# LTC2949_Connectors.net
KiCad netlist of a schematic drawn in Altium Designer
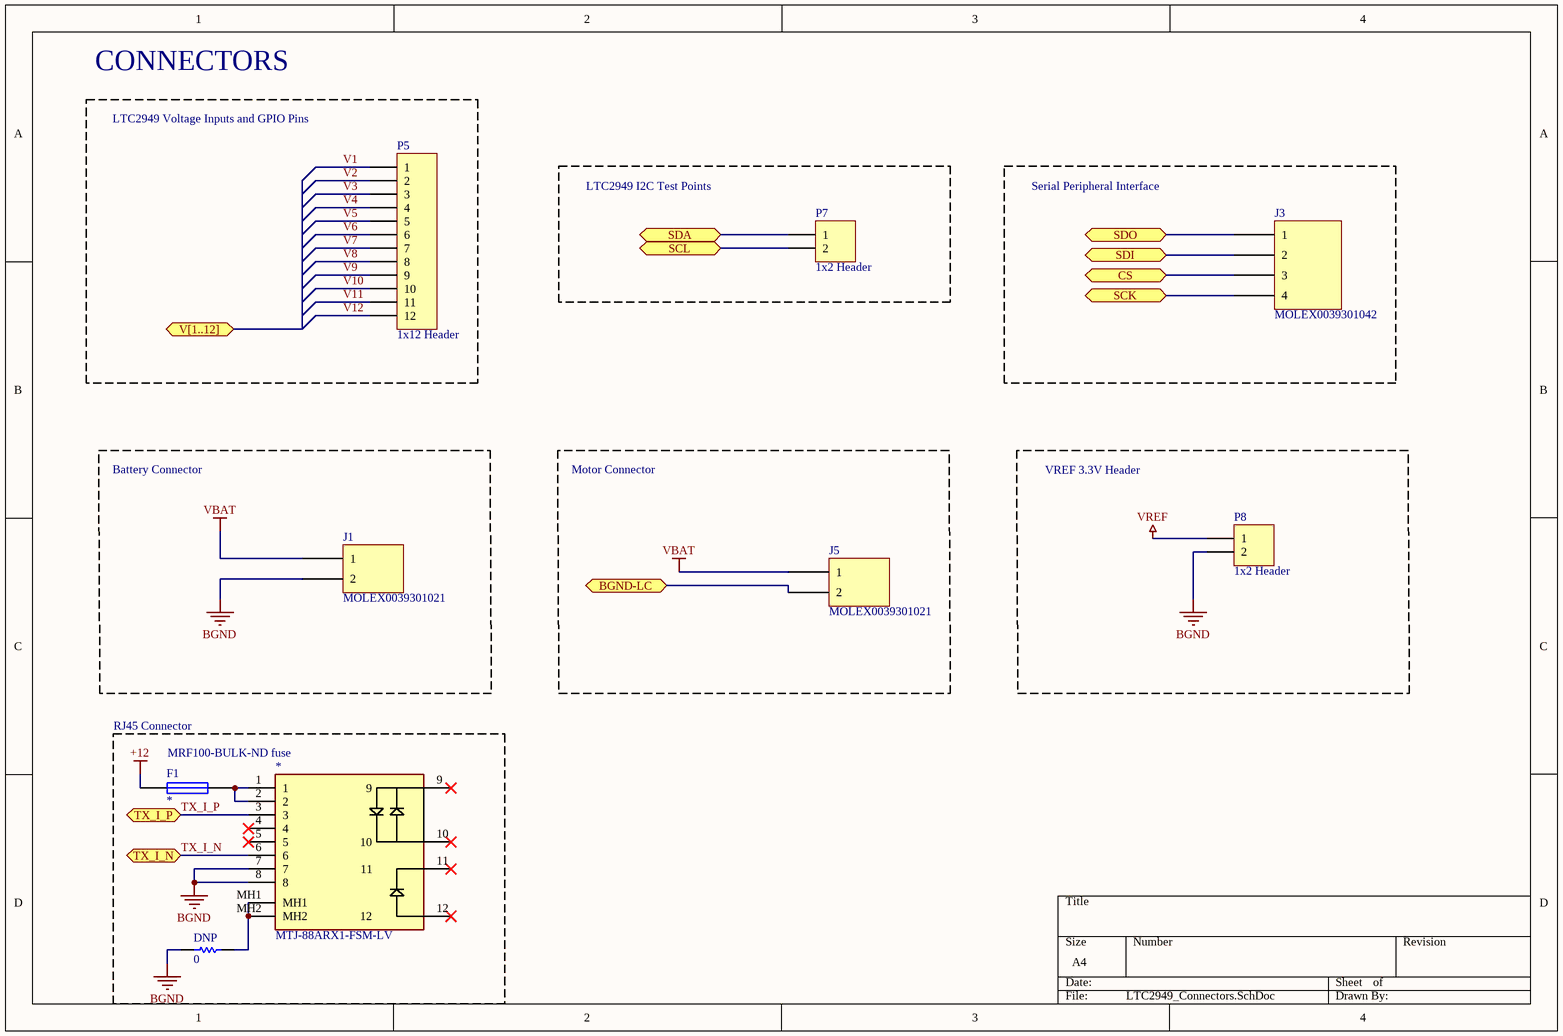
[diagram p0: LTC2949_Connectors.SchDoc]

(export (version "E")
  (design (tool "Eeschema 10.0.6"))
  (components
    (comp (ref "*")
      (value "MTJ-88ARX1-FSM-LV")
      (footprint "MTJ-88ARX1-FSM-LV")
      (description "RJ45 Connector")
      (libsource (lib "GeneralConnectors") (part "MTJ-88ARX1-FSM-LV"))
    )
    (comp (ref "DNP")
      (value "0")
      (footprint "0603 - Resistor")
      (description "Resistor")
      (libsource (lib "General") (part "Resistor"))
    )
    (comp (ref "F1")
      (value "Fuse")
      (footprint "3557-2")
      (fields (field (name "ALTIUM_VALUE") "*"))
      (libsource (lib "General") (part "Fuse"))
    )
    (comp (ref "J1")
      (value "MOLEX0039301021")
      (footprint "MOLEX0039301021")
      (description "Connector Header Through Hole, Right Angle 2 pin 0.165\" (4.20mm)")
      (libsource (lib "GeneralConnectors") (part "MOLEX0039301021"))
    )
    (comp (ref "J3")
      (value "MOLEX0039301042")
      (footprint "MOLEX0039301042")
      (description "Connector Header Through Hole, Right Angle 4 position 0.165\" (4.20mm)")
      (fields (field (name "MANUFACTURER") "Molex") (field (name "MANUFACTURER PART NUMBER") "0039301042"))
      (libsource (lib "GeneralConnectors") (part "MOLEX0039301042"))
    )
    (comp (ref "J5")
      (value "MOLEX0039301021")
      (footprint "MOLEX0039301021")
      (description "Connector Header Through Hole, Right Angle 2 pin 0.165\" (4.20mm)")
      (libsource (lib "GeneralConnectors") (part "MOLEX0039301021"))
    )
    (comp (ref "P5")
      (value "1x12 Header")
      (footprint "HDR1X12")
      (description "1x12 Pin Header")
      (libsource (lib "GeneralConnectors") (part "1x12 Header"))
    )
    (comp (ref "P7")
      (value "1x2 Header")
      (footprint "HDR1X2")
      (description "1x2 Pin Header")
      (libsource (lib "GeneralConnectors") (part "1x2 Header"))
    )
    (comp (ref "P8")
      (value "1x2 Header")
      (footprint "HDR1X2")
      (description "1x2 Pin Header")
      (libsource (lib "GeneralConnectors") (part "1x2 Header"))
    )
  )
  (nets
    (net (code "1") (name "+12") (class "Default")
      (node (ref "F1") (pin "1") (pinfunction "1_1") (pintype "passive"))
    )
    (net (code "2") (name "/BGND-LC") (class "Default")
      (node (ref "J5") (pin "2") (pinfunction "2_2") (pintype "passive"))
    )
    (net (code "3") (name "/CS") (class "Default")
      (node (ref "J3") (pin "3") (pinfunction "3_3") (pintype "passive"))
    )
    (net (code "4") (name "/SCK") (class "Default")
      (node (ref "J3") (pin "4") (pinfunction "4_4") (pintype "passive"))
    )
    (net (code "5") (name "/SCL") (class "Default")
      (node (ref "P7") (pin "2") (pinfunction "2_2") (pintype "passive"))
    )
    (net (code "6") (name "/SDA") (class "Default")
      (node (ref "P7") (pin "1") (pinfunction "1_1") (pintype "passive"))
    )
    (net (code "7") (name "/SDI") (class "Default")
      (node (ref "J3") (pin "2") (pinfunction "2_2") (pintype "passive"))
    )
    (net (code "8") (name "/SDO") (class "Default")
      (node (ref "J3") (pin "1") (pinfunction "1_1") (pintype "passive"))
    )
    (net (code "9") (name "/TX_I_N") (class "Default")
      (node (ref "*") (pin "6") (pinfunction "6_6") (pintype "passive"))
    )
    (net (code "10") (name "/TX_I_P") (class "Default")
      (node (ref "*") (pin "3") (pinfunction "3_3") (pintype "passive"))
    )
    (net (code "11") (name "/V1") (class "Default")
      (node (ref "P5") (pin "1") (pinfunction "1_1") (pintype "passive"))
    )
    (net (code "12") (name "/V2") (class "Default")
      (node (ref "P5") (pin "2") (pinfunction "2_2") (pintype "passive"))
    )
    (net (code "13") (name "/V3") (class "Default")
      (node (ref "P5") (pin "3") (pinfunction "3_3") (pintype "passive"))
    )
    (net (code "14") (name "/V4") (class "Default")
      (node (ref "P5") (pin "4") (pinfunction "4_4") (pintype "passive"))
    )
    (net (code "15") (name "/V5") (class "Default")
      (node (ref "P5") (pin "5") (pinfunction "5_5") (pintype "passive"))
    )
    (net (code "16") (name "/V6") (class "Default")
      (node (ref "P5") (pin "6") (pinfunction "6_6") (pintype "passive"))
    )
    (net (code "17") (name "/V7") (class "Default")
      (node (ref "P5") (pin "7") (pinfunction "7_7") (pintype "passive"))
    )
    (net (code "18") (name "/V8") (class "Default")
      (node (ref "P5") (pin "8") (pinfunction "8_8") (pintype "passive"))
    )
    (net (code "19") (name "/V9") (class "Default")
      (node (ref "P5") (pin "9") (pinfunction "9_9") (pintype "passive"))
    )
    (net (code "20") (name "/V10") (class "Default")
      (node (ref "P5") (pin "10") (pinfunction "10_10") (pintype "passive"))
    )
    (net (code "21") (name "/V11") (class "Default")
      (node (ref "P5") (pin "11") (pinfunction "11_11") (pintype "passive"))
    )
    (net (code "22") (name "/V12") (class "Default")
      (node (ref "P5") (pin "12") (pinfunction "12_12") (pintype "passive"))
    )
    (net (code "24") (name "BGND") (class "Default")
      (node (ref "*") (pin "7") (pinfunction "7_7") (pintype "passive"))
      (node (ref "*") (pin "8") (pinfunction "8_8") (pintype "passive"))
      (node (ref "DNP") (pin "1") (pinfunction "1_1") (pintype "passive"))
      (node (ref "J1") (pin "2") (pinfunction "2_2") (pintype "passive"))
      (node (ref "P8") (pin "2") (pinfunction "2_2") (pintype "passive"))
    )
    (net (code "25") (name "Net-(*-Pad1)") (class "Default")
      (node (ref "*") (pin "1") (pinfunction "1_1") (pintype "passive"))
      (node (ref "*") (pin "2") (pinfunction "2_2") (pintype "passive"))
      (node (ref "F1") (pin "2") (pinfunction "2_2") (pintype "passive"))
    )
    (net (code "26") (name "Net-(*-PadMH1)") (class "Default")
      (node (ref "*") (pin "MH1") (pinfunction "MH1_MH1") (pintype "passive"))
      (node (ref "*") (pin "MH2") (pinfunction "MH2_MH2") (pintype "passive"))
      (node (ref "DNP") (pin "2") (pinfunction "2_2") (pintype "passive"))
    )
    (net (code "27") (name "VBAT") (class "Default")
      (node (ref "J1") (pin "1") (pinfunction "1_1") (pintype "passive"))
      (node (ref "J5") (pin "1") (pinfunction "1_1") (pintype "passive"))
    )
    (net (code "28") (name "VREF") (class "Default")
      (node (ref "P8") (pin "1") (pinfunction "1_1") (pintype "passive"))
    )
    (net (code "29") (name "unconnected-(*-Pad4)") (class "Default")
      (node (ref "*") (pin "4") (pinfunction "4_4") (pintype "passive+no_connect"))
    )
    (net (code "30") (name "unconnected-(*-Pad5)") (class "Default")
      (node (ref "*") (pin "5") (pinfunction "5_5") (pintype "passive+no_connect"))
    )
    (net (code "31") (name "unconnected-(*-Pad9)") (class "Default")
      (node (ref "*") (pin "9") (pinfunction "9_9") (pintype "passive+no_connect"))
    )
    (net (code "32") (name "unconnected-(*-Pad10)") (class "Default")
      (node (ref "*") (pin "10") (pinfunction "10_10") (pintype "passive+no_connect"))
    )
    (net (code "33") (name "unconnected-(*-Pad11)") (class "Default")
      (node (ref "*") (pin "11") (pinfunction "11_11") (pintype "passive+no_connect"))
    )
    (net (code "34") (name "unconnected-(*-Pad12)") (class "Default")
      (node (ref "*") (pin "12") (pinfunction "12_12") (pintype "passive+no_connect"))
    )
  )
)
